# my-cnc.net
KiCad netlist of a schematic drawn in Altium Designer
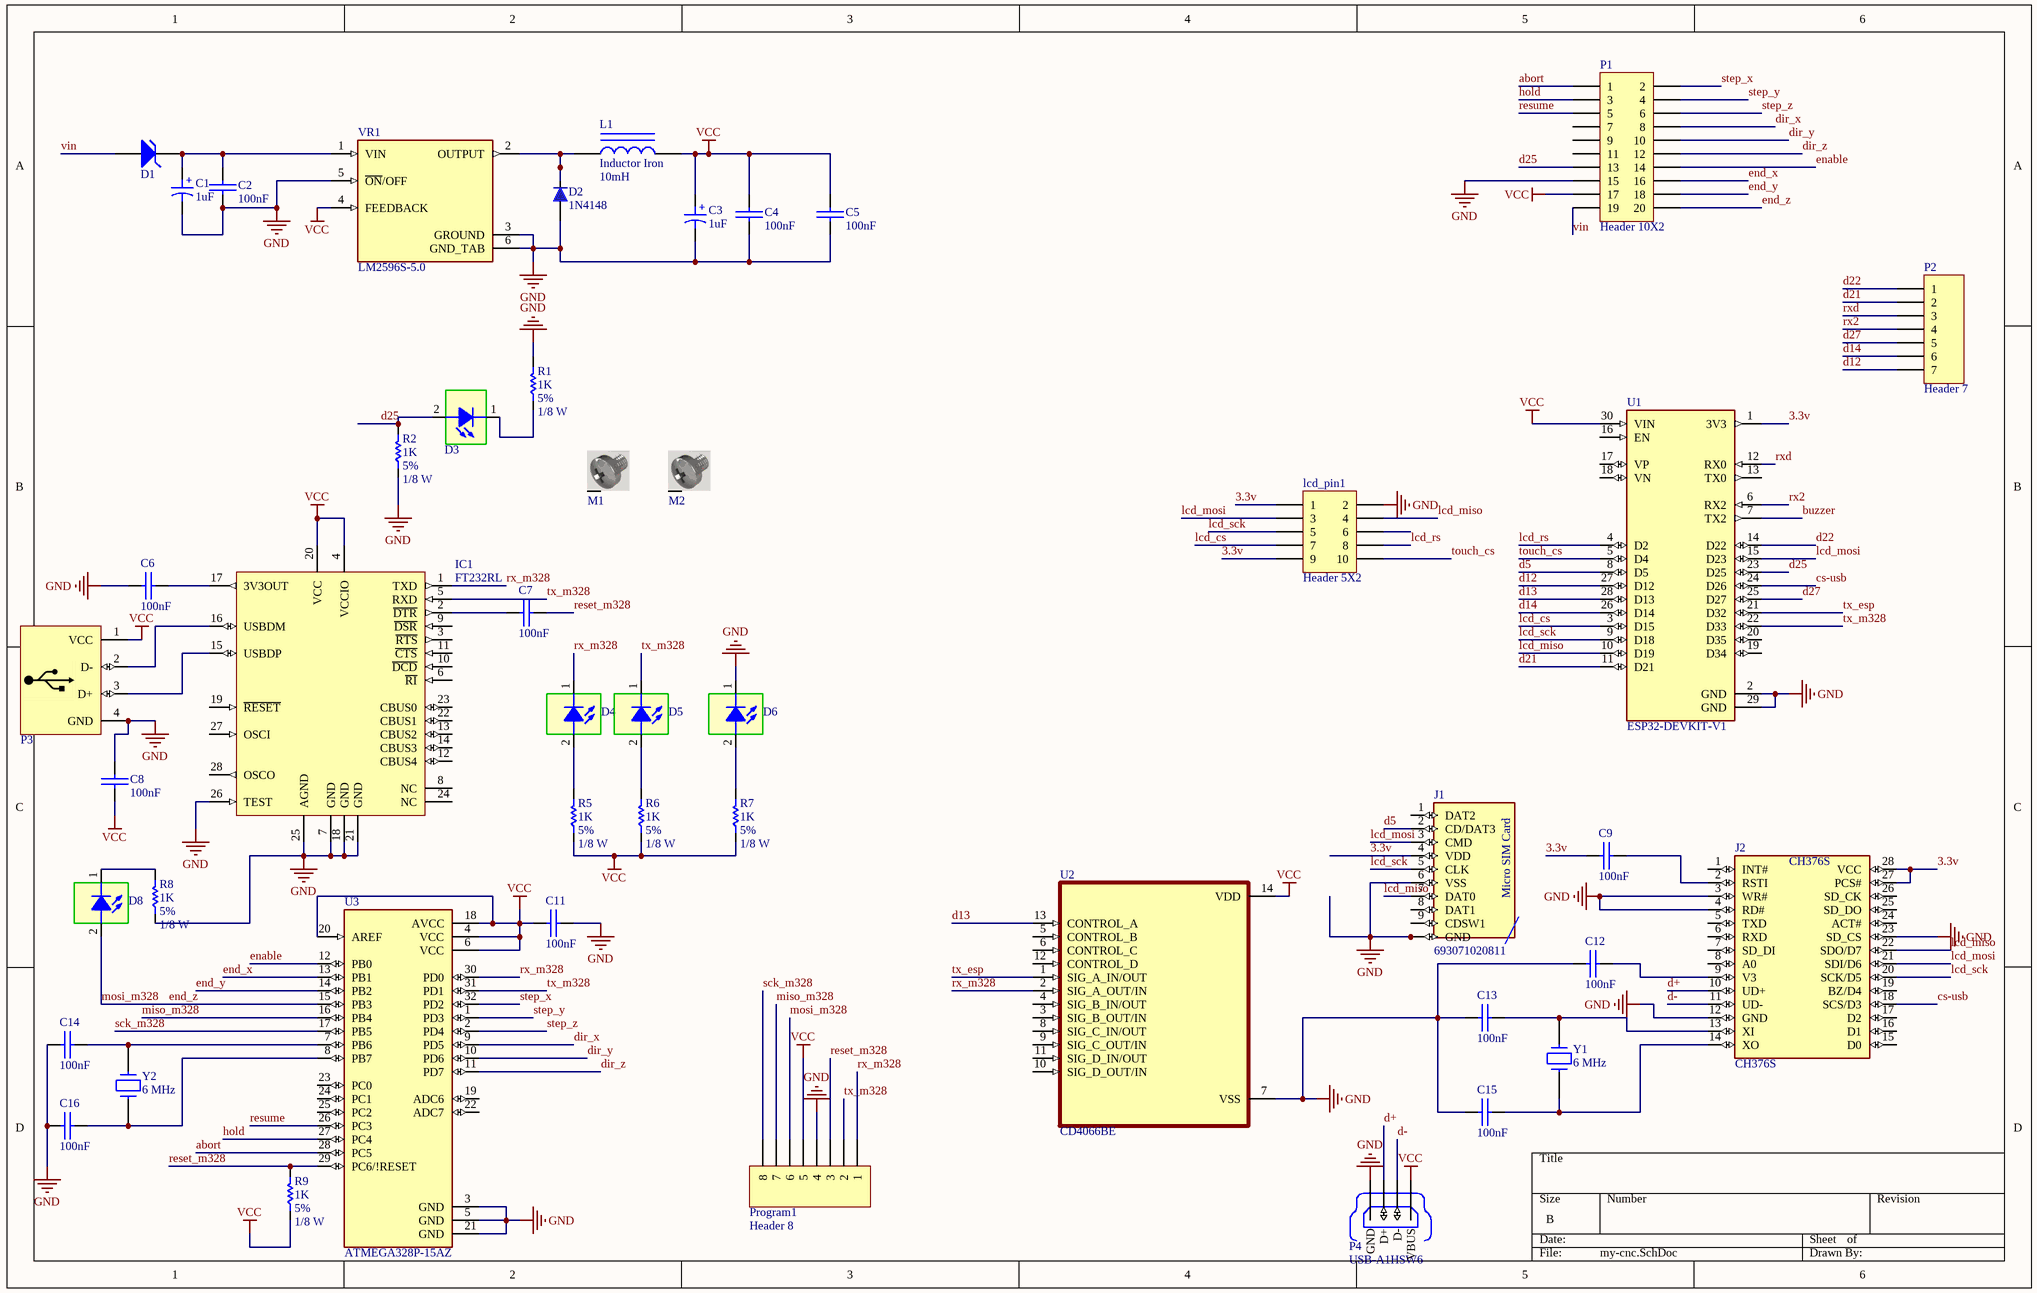
[diagram p0: my-cnc.SchDoc]

(export (version "E")
  (design (tool "Eeschema 10.0.6"))
  (components
    (comp (ref "C1")
      (value "1uF")
      (footprint "CAP SMD 470uF")
      (description "Cap electrolitic radial")
      (fields (field (name "DESIGNER") "Abbas Basereh"))
      (libsource (lib "Altium") (part "Cap ELECTROLITIC TOTAL SIZE"))
    )
    (comp (ref "C2")
      (value "100nF")
      (footprint "SMD_CAP_1206")
      (description "Bipolar Capacitor")
      (fields (field (name "VOLTAGE") "100V") (field (name "DESIGNER") "Saeid Jorablo"))
      (libsource (lib "My_Library") (part "Cap-Bipolar"))
    )
    (comp (ref "C3")
      (value "1uF")
      (footprint "CAP SMD 470uF")
      (description "Cap electrolitic radial")
      (fields (field (name "DESIGNER") "Abbas Basereh"))
      (libsource (lib "Altium") (part "Cap ELECTROLITIC TOTAL SIZE"))
    )
    (comp (ref "C4")
      (value "100nF")
      (footprint "SMD_CAP_1206")
      (description "Bipolar Capacitor")
      (fields (field (name "VOLTAGE") "100V") (field (name "DESIGNER") "Saeid Jorablo"))
      (libsource (lib "My_Library") (part "Cap-Bipolar"))
    )
    (comp (ref "C5")
      (value "100nF")
      (footprint "SMD_CAP_1206")
      (description "Bipolar Capacitor")
      (fields (field (name "VOLTAGE") "100V") (field (name "DESIGNER") "Saeid Jorablo"))
      (libsource (lib "My_Library") (part "Cap-Bipolar"))
    )
    (comp (ref "C6")
      (value "100nF")
      (footprint "SMD_CAP_1206")
      (description "Bipolar Capacitor")
      (fields (field (name "VOLTAGE") "100V") (field (name "DESIGNER") "Saeid Jorablo"))
      (libsource (lib "My_Library") (part "Cap-Bipolar"))
    )
    (comp (ref "C7")
      (value "100nF")
      (footprint "SMD_CAP_1206")
      (description "Bipolar Capacitor")
      (fields (field (name "VOLTAGE") "100V") (field (name "DESIGNER") "Saeid Jorablo"))
      (libsource (lib "My_Library") (part "Cap-Bipolar"))
    )
    (comp (ref "C8")
      (value "100nF")
      (footprint "SMD_CAP_1206")
      (description "Bipolar Capacitor")
      (fields (field (name "VOLTAGE") "100V") (field (name "DESIGNER") "Saeid Jorablo"))
      (libsource (lib "My_Library") (part "Cap-Bipolar"))
    )
    (comp (ref "C9")
      (value "100nF")
      (footprint "SMD_CAP_1206")
      (description "Bipolar Capacitor")
      (fields (field (name "VOLTAGE") "100V") (field (name "DESIGNER") "Saeid Jorablo"))
      (libsource (lib "My_Library") (part "Cap-Bipolar"))
    )
    (comp (ref "C11")
      (value "100nF")
      (footprint "SMD_CAP_1206")
      (description "Bipolar Capacitor")
      (fields (field (name "VOLTAGE") "100V") (field (name "DESIGNER") "Saeid Jorablo"))
      (libsource (lib "My_Library") (part "Cap-Bipolar"))
    )
    (comp (ref "C12")
      (value "100nF")
      (footprint "SMD_CAP_1206")
      (description "Bipolar Capacitor")
      (fields (field (name "VOLTAGE") "100V") (field (name "DESIGNER") "Saeid Jorablo"))
      (libsource (lib "My_Library") (part "Cap-Bipolar"))
    )
    (comp (ref "C13")
      (value "100nF")
      (footprint "SMD_CAP_1206")
      (description "Bipolar Capacitor")
      (fields (field (name "VOLTAGE") "100V") (field (name "DESIGNER") "Saeid Jorablo"))
      (libsource (lib "My_Library") (part "Cap-Bipolar"))
    )
    (comp (ref "C14")
      (value "100nF")
      (footprint "SMD_CAP_1206")
      (description "Bipolar Capacitor")
      (fields (field (name "VOLTAGE") "100V") (field (name "DESIGNER") "Saeid Jorablo"))
      (libsource (lib "My_Library") (part "Cap-Bipolar"))
    )
    (comp (ref "C15")
      (value "100nF")
      (footprint "SMD_CAP_1206")
      (description "Bipolar Capacitor")
      (fields (field (name "VOLTAGE") "100V") (field (name "DESIGNER") "Saeid Jorablo"))
      (libsource (lib "My_Library") (part "Cap-Bipolar"))
    )
    (comp (ref "C16")
      (value "100nF")
      (footprint "SMD_CAP_1206")
      (description "Bipolar Capacitor")
      (fields (field (name "VOLTAGE") "100V") (field (name "DESIGNER") "Saeid Jorablo"))
      (libsource (lib "My_Library") (part "Cap-Bipolar"))
    )
    (comp (ref "D1")
      (value "Diode Zener")
      (footprint "Diode 1W")
      (description "Zener Diode")
      (fields (field (name "VOLTAGE") "3.3 V") (field (name "DESIGNER") "Saeid Jorablo"))
      (libsource (lib "My_Library") (part "Diode Zener"))
    )
    (comp (ref "D2")
      (value "1N4148")
      (footprint "Diode 1n4148 SMD")
      (description "General Semicoductor")
      (libsource (lib "Altium") (part "1N4148 SMD"))
    )
    (comp (ref "D3")
      (value "SMD 1206 LED")
      (footprint "LED 1206")
      (libsource (lib "") (part "LED SMD 1206_1"))
    )
    (comp (ref "D4")
      (value "SMD 1206 LED")
      (footprint "LED 1206")
      (libsource (lib "Altium") (part "LED SMD 1206"))
    )
    (comp (ref "D5")
      (value "SMD 1206 LED")
      (footprint "LED 1206")
      (libsource (lib "Altium") (part "LED SMD 1206"))
    )
    (comp (ref "D6")
      (value "SMD 1206 LED")
      (footprint "LED 1206")
      (libsource (lib "Altium") (part "LED SMD 1206"))
    )
    (comp (ref "D8")
      (value "SMD 1206 LED")
      (footprint "LED 1206")
      (libsource (lib "Altium") (part "LED SMD 1206"))
    )
    (comp (ref "IC1")
      (value "FT232RL")
      (footprint "SSOP-28_L")
      (description "USB UART Asynchronous Serial Data Transfer Chip, SSOP-28, Tape and Reel")
      (fields (field (name "PUBLISHER") "Altium Limited"))
      (libsource (lib "Altium") (part "FT232RL"))
    )
    (comp (ref "J1")
      (value "693071020811")
      (footprint "693071020811")
      (description "9 (8 + 1) Position Card Connector Secure Digital - microSDâ„¢ Surface Mount, Right Angle Gold")
      (fields (field (name "MF") "Wurth Electronics"))
      (libsource (lib "693071020811") (part "693071020811"))
    )
    (comp (ref "J2")
      (value "CH376S")
      (footprint "SOP28")
      (description "File manage control chip. Small outline package of 28-pin")
      (fields (field (name "MF") "WCH"))
      (libsource (lib "CH376S") (part "CH376S"))
    )
    (comp (ref "L1")
      (value "Inductor Iron")
      (footprint "AXIAL-0.9")
      (description "Magnetic-Core Inductor")
      (fields (field (name "ALTIUM_VALUE") "10mH") (field (name "PUBLISHER") "Altium Limited"))
      (libsource (lib "Miscellaneous Devices") (part "Inductor Iron"))
    )
    (comp (ref "lcd_pin1")
      (value "Header 5X2")
      (footprint "HDR2X5")
      (description "Header, 5-Pin, Dual row")
      (fields (field (name "PUBLISHER") "Altium Limited"))
      (libsource (lib "Miscellaneous Connectors") (part "Header 5X2"))
    )
    (comp (ref "M1")
      (value "Screw")
      (footprint "Board Screw")
      (description "Board Screw With Spacer")
      (libsource (lib "My_Library") (part "Board Screw"))
    )
    (comp (ref "M2")
      (value "Screw")
      (footprint "Board Screw")
      (description "Board Screw With Spacer")
      (libsource (lib "My_Library") (part "Board Screw"))
    )
    (comp (ref "P1")
      (value "Header 10X2")
      (footprint "HDR2X10")
      (description "Header, 10-Pin, Dual row")
      (fields (field (name "PUBLISHER") "Altium Limited"))
      (libsource (lib "Miscellaneous Connectors") (part "Header 10X2"))
    )
    (comp (ref "P2")
      (value "Header 7")
      (footprint "HDR1X7")
      (description "Header, 7-Pin")
      (fields (field (name "PUBLISHER") "Altium Limited"))
      (libsource (lib "Miscellaneous Connectors") (part "Header 7"))
    )
    (comp (ref "P3")
      (value "USB Connector")
      (footprint "USB2.5-2H4F")
      (description "USB Connector-B Type")
      (libsource (lib "Altium") (part "USB B-Type"))
    )
    (comp (ref "P4")
      (value "USB-A1HSW6")
      (footprint "OST_USB-A1HSW6")
      (description "USB-A (USB TYPE-A) - Receptacle Connector 4 Position Through Hole, Right Angle")
      (fields (field (name "MF") "On Shore"))
      (libsource (lib "USB-A1HSW6") (part "USB-A1HSW6"))
    )
    (comp (ref "Program1")
      (value "Header 8")
      (footprint "HDR1X8")
      (description "Header, 8-Pin")
      (fields (field (name "PUBLISHER") "Altium Limited"))
      (libsource (lib "Miscellaneous Connectors") (part "Header 8"))
    )
    (comp (ref "R1")
      (value "1K")
      (footprint "RES 1206 (3216X08L)")
      (description "Resistor")
      (fields (field (name "TOLERANCE") "5%") (field (name "POWER") "1/8 W"))
      (libsource (lib "My_Library") (part "Resistor"))
    )
    (comp (ref "R2")
      (value "1K")
      (footprint "RES 1206 (3216X08L)")
      (description "Resistor")
      (fields (field (name "TOLERANCE") "5%") (field (name "POWER") "1/8 W"))
      (libsource (lib "My_Library") (part "Resistor"))
    )
    (comp (ref "R5")
      (value "1K")
      (footprint "RES 1206 (3216X08L)")
      (description "Resistor")
      (fields (field (name "TOLERANCE") "5%") (field (name "POWER") "1/8 W"))
      (libsource (lib "My_Library") (part "Resistor"))
    )
    (comp (ref "R6")
      (value "1K")
      (footprint "RES 1206 (3216X08L)")
      (description "Resistor")
      (fields (field (name "TOLERANCE") "5%") (field (name "POWER") "1/8 W"))
      (libsource (lib "My_Library") (part "Resistor"))
    )
    (comp (ref "R7")
      (value "1K")
      (footprint "RES 1206 (3216X08L)")
      (description "Resistor")
      (fields (field (name "TOLERANCE") "5%") (field (name "POWER") "1/8 W"))
      (libsource (lib "My_Library") (part "Resistor"))
    )
    (comp (ref "R8")
      (value "1K")
      (footprint "RES 1206 (3216X08L)")
      (description "Resistor")
      (fields (field (name "TOLERANCE") "5%") (field (name "POWER") "1/8 W"))
      (libsource (lib "My_Library") (part "Resistor"))
    )
    (comp (ref "R9")
      (value "1K")
      (footprint "RES 1206 (3216X08L)")
      (description "Resistor")
      (fields (field (name "TOLERANCE") "5%") (field (name "POWER") "1/8 W"))
      (libsource (lib "My_Library") (part "Resistor"))
    )
    (comp (ref "U1")
      (value "ESP32-DEVKIT-V1")
      (footprint "MODULE_ESP32_DEVKIT_V1")
      (fields (field (name "MF") "Do it"))
      (libsource (lib "ESP32-DEVKIT-V1") (part "ESP32-DEVKIT-V1"))
    )
    (comp (ref "U2")
      (value "CD4066BE")
      (footprint "DIP794W45P254L1969H508Q14")
      (description "10-pA on-state leakage current, 20-V, 1:1 (SPST), 4-channel analog switch")
      (fields (field (name "MF") "Texas Instruments"))
      (libsource (lib "CD4066BE") (part "CD4066BE"))
    )
    (comp (ref "U3")
      (value "ATMEGA328P-15AZ")
      (footprint "QFP80P900X900X120-32N")
      (fields (field (name "MF") "Microchip") (field (name "DIGI-KEY_PART_NUMBER") "ATMEGA328P-15AZCT-ND"))
      (libsource (lib "ATMEGA328P-15AZ") (part "ATMEGA328P-15AZ"))
    )
    (comp (ref "VR1")
      (value "LM2596S-5.0")
      (footprint "LM2596S-5.0:TO170P1524X483-6N")
      (libsource (lib "LM2596S-5.0") (part "LM2596S-5.0"))
    )
    (comp (ref "Y1")
      (value "6 MHz")
      (footprint "My_Crystal")
      (description "Crystal")
      (libsource (lib "Devices") (part "CRYSTAL"))
    )
    (comp (ref "Y2")
      (value "6 MHz")
      (footprint "My_Crystal")
      (description "Crystal")
      (libsource (lib "Devices") (part "CRYSTAL"))
    )
  )
  (nets
    (net (code "1") (name "/3.3v") (class "Default")
      (node (ref "C9") (pin "2") (pinfunction "-_2") (pintype "passive"))
      (node (ref "J1") (pin "4") (pinfunction "VDD_4") (pintype "bidirectional"))
      (node (ref "J2") (pin "27") (pinfunction "PCS#_27") (pintype "bidirectional"))
      (node (ref "J2") (pin "28") (pinfunction "VCC_28") (pintype "bidirectional"))
      (node (ref "U1") (pin "1") (pinfunction "3V3_1") (pintype "output"))
      (node (ref "lcd_pin1") (pin "1") (pinfunction "1_1") (pintype "passive"))
      (node (ref "lcd_pin1") (pin "9") (pinfunction "9_9") (pintype "passive"))
    )
    (net (code "2") (name "/abort") (class "Default")
      (node (ref "P1") (pin "1") (pinfunction "1_1") (pintype "passive"))
      (node (ref "U3") (pin "28") (pinfunction "PC5_28") (pintype "bidirectional"))
    )
    (net (code "3") (name "/buzzer") (class "Default")
      (node (ref "U1") (pin "7") (pinfunction "TX2_7") (pintype "output"))
    )
    (net (code "4") (name "/cs-usb") (class "Default")
      (node (ref "J2") (pin "18") (pinfunction "SCS/D3_18") (pintype "bidirectional"))
      (node (ref "U1") (pin "24") (pinfunction "D26_24") (pintype "bidirectional"))
    )
    (net (code "5") (name "/d+") (class "Default")
      (node (ref "J2") (pin "10") (pinfunction "UD+_10") (pintype "bidirectional"))
      (node (ref "P4") (pin "3") (pinfunction "D+_3") (pintype "bidirectional"))
    )
    (net (code "6") (name "/d-") (class "Default")
      (node (ref "J2") (pin "11") (pinfunction "UD-_11") (pintype "bidirectional"))
      (node (ref "P4") (pin "2") (pinfunction "D-_2") (pintype "bidirectional"))
    )
    (net (code "7") (name "/d5") (class "Default")
      (node (ref "J1") (pin "2") (pinfunction "CD/DAT3_2") (pintype "bidirectional"))
      (node (ref "U1") (pin "8") (pinfunction "D5_8") (pintype "bidirectional"))
    )
    (net (code "8") (name "/d12") (class "Default")
      (node (ref "P2") (pin "7") (pinfunction "7_7") (pintype "passive"))
      (node (ref "U1") (pin "27") (pinfunction "D12_27") (pintype "bidirectional"))
    )
    (net (code "9") (name "/d13") (class "Default")
      (node (ref "U1") (pin "28") (pinfunction "D13_28") (pintype "bidirectional"))
      (node (ref "U2") (pin "13") (pinfunction "CONTROL_A_13") (pintype "input"))
    )
    (net (code "10") (name "/d14") (class "Default")
      (node (ref "P2") (pin "6") (pinfunction "6_6") (pintype "passive"))
      (node (ref "U1") (pin "26") (pinfunction "D14_26") (pintype "bidirectional"))
    )
    (net (code "11") (name "/d21") (class "Default")
      (node (ref "P2") (pin "2") (pinfunction "2_2") (pintype "passive"))
      (node (ref "U1") (pin "11") (pinfunction "D21_11") (pintype "bidirectional"))
    )
    (net (code "12") (name "/d22") (class "Default")
      (node (ref "P2") (pin "1") (pinfunction "1_1") (pintype "passive"))
      (node (ref "U1") (pin "14") (pinfunction "D22_14") (pintype "bidirectional"))
    )
    (net (code "13") (name "/d25") (class "Default")
      (node (ref "D3") (pin "2") (pinfunction "2_2") (pintype "passive"))
      (node (ref "P1") (pin "13") (pinfunction "13_13") (pintype "passive"))
      (node (ref "R2") (pin "2") (pinfunction "2_2") (pintype "passive"))
      (node (ref "U1") (pin "23") (pinfunction "D25_23") (pintype "bidirectional"))
    )
    (net (code "14") (name "/d27") (class "Default")
      (node (ref "P2") (pin "5") (pinfunction "5_5") (pintype "passive"))
      (node (ref "U1") (pin "25") (pinfunction "D27_25") (pintype "bidirectional"))
    )
    (net (code "15") (name "/dir_x") (class "Default")
      (node (ref "P1") (pin "8") (pinfunction "8_8") (pintype "passive"))
      (node (ref "U3") (pin "9") (pinfunction "PD5_9") (pintype "bidirectional"))
    )
    (net (code "16") (name "/dir_y") (class "Default")
      (node (ref "P1") (pin "10") (pinfunction "10_10") (pintype "passive"))
      (node (ref "U3") (pin "10") (pinfunction "PD6_10") (pintype "bidirectional"))
    )
    (net (code "17") (name "/dir_z") (class "Default")
      (node (ref "P1") (pin "12") (pinfunction "12_12") (pintype "passive"))
      (node (ref "U3") (pin "11") (pinfunction "PD7_11") (pintype "bidirectional"))
    )
    (net (code "18") (name "/enable") (class "Default")
      (node (ref "P1") (pin "14") (pinfunction "14_14") (pintype "passive"))
      (node (ref "U3") (pin "12") (pinfunction "PB0_12") (pintype "bidirectional"))
    )
    (net (code "19") (name "/end_x") (class "Default")
      (node (ref "P1") (pin "16") (pinfunction "16_16") (pintype "passive"))
      (node (ref "U3") (pin "13") (pinfunction "PB1_13") (pintype "bidirectional"))
    )
    (net (code "20") (name "/end_y") (class "Default")
      (node (ref "P1") (pin "18") (pinfunction "18_18") (pintype "passive"))
      (node (ref "U3") (pin "14") (pinfunction "PB2_14") (pintype "bidirectional"))
    )
    (net (code "21") (name "/end_z") (class "Default")
      (node (ref "D8") (pin "2") (pinfunction "2_2") (pintype "passive"))
      (node (ref "P1") (pin "20") (pinfunction "20_20") (pintype "passive"))
      (node (ref "Program1") (pin "6") (pinfunction "6_6") (pintype "passive"))
      (node (ref "U3") (pin "15") (pinfunction "PB3_15") (pintype "bidirectional"))
    )
    (net (code "22") (name "/hold") (class "Default")
      (node (ref "P1") (pin "3") (pinfunction "3_3") (pintype "passive"))
      (node (ref "U3") (pin "27") (pinfunction "PC4_27") (pintype "bidirectional"))
    )
    (net (code "23") (name "/lcd_cs") (class "Default")
      (node (ref "U1") (pin "3") (pinfunction "D15_3") (pintype "bidirectional"))
      (node (ref "lcd_pin1") (pin "7") (pinfunction "7_7") (pintype "passive"))
    )
    (net (code "24") (name "/lcd_miso") (class "Default")
      (node (ref "J1") (pin "7") (pinfunction "DAT0_7") (pintype "bidirectional"))
      (node (ref "J2") (pin "22") (pinfunction "SDO/D7_22") (pintype "bidirectional"))
      (node (ref "U1") (pin "10") (pinfunction "D19_10") (pintype "bidirectional"))
      (node (ref "lcd_pin1") (pin "4") (pinfunction "4_4") (pintype "passive"))
    )
    (net (code "25") (name "/lcd_mosi") (class "Default")
      (node (ref "J1") (pin "3") (pinfunction "CMD_3") (pintype "bidirectional"))
      (node (ref "J2") (pin "21") (pinfunction "SDI/D6_21") (pintype "bidirectional"))
      (node (ref "U1") (pin "15") (pinfunction "D23_15") (pintype "bidirectional"))
      (node (ref "lcd_pin1") (pin "3") (pinfunction "3_3") (pintype "passive"))
    )
    (net (code "26") (name "/lcd_rs") (class "Default")
      (node (ref "U1") (pin "4") (pinfunction "D2_4") (pintype "bidirectional"))
      (node (ref "lcd_pin1") (pin "8") (pinfunction "8_8") (pintype "passive"))
    )
    (net (code "27") (name "/lcd_sck") (class "Default")
      (node (ref "J1") (pin "5") (pinfunction "CLK_5") (pintype "bidirectional"))
      (node (ref "J2") (pin "20") (pinfunction "SCK/D5_20") (pintype "bidirectional"))
      (node (ref "U1") (pin "9") (pinfunction "D18_9") (pintype "bidirectional"))
      (node (ref "lcd_pin1") (pin "5") (pinfunction "5_5") (pintype "passive"))
    )
    (net (code "28") (name "/miso_m328") (class "Default")
      (node (ref "Program1") (pin "7") (pinfunction "7_7") (pintype "passive"))
      (node (ref "U3") (pin "16") (pinfunction "PB4_16") (pintype "bidirectional"))
    )
    (net (code "29") (name "/reset_m328") (class "Default")
      (node (ref "C7") (pin "1") (pinfunction "+_1") (pintype "passive"))
      (node (ref "Program1") (pin "3") (pinfunction "3_3") (pintype "passive"))
      (node (ref "R9") (pin "2") (pinfunction "2_2") (pintype "passive"))
      (node (ref "U3") (pin "29") (pinfunction "PC6/!RESET_29") (pintype "bidirectional"))
    )
    (net (code "30") (name "/resume") (class "Default")
      (node (ref "P1") (pin "5") (pinfunction "5_5") (pintype "passive"))
      (node (ref "U3") (pin "26") (pinfunction "PC3_26") (pintype "bidirectional"))
    )
    (net (code "31") (name "/rx2") (class "Default")
      (node (ref "P2") (pin "4") (pinfunction "4_4") (pintype "passive"))
      (node (ref "U1") (pin "6") (pinfunction "RX2_6") (pintype "input"))
    )
    (net (code "32") (name "/rx_m328") (class "Default")
      (node (ref "D4") (pin "1") (pinfunction "1_1") (pintype "passive"))
      (node (ref "IC1") (pin "1") (pinfunction "TXD_1") (pintype "output"))
      (node (ref "Program1") (pin "1") (pinfunction "1_1") (pintype "passive"))
      (node (ref "U2") (pin "2") (pinfunction "SIG_A_OUT/IN_2") (pintype "input"))
      (node (ref "U3") (pin "30") (pinfunction "PD0_30") (pintype "bidirectional"))
    )
    (net (code "33") (name "/rxd") (class "Default")
      (node (ref "P2") (pin "3") (pinfunction "3_3") (pintype "passive"))
      (node (ref "U1") (pin "12") (pinfunction "RX0_12") (pintype "input"))
    )
    (net (code "34") (name "/sck_m328") (class "Default")
      (node (ref "Program1") (pin "8") (pinfunction "8_8") (pintype "passive"))
      (node (ref "U3") (pin "17") (pinfunction "PB5_17") (pintype "bidirectional"))
    )
    (net (code "35") (name "/step_x") (class "Default")
      (node (ref "P1") (pin "2") (pinfunction "2_2") (pintype "passive"))
      (node (ref "U3") (pin "32") (pinfunction "PD2_32") (pintype "bidirectional"))
    )
    (net (code "36") (name "/step_y") (class "Default")
      (node (ref "P1") (pin "4") (pinfunction "4_4") (pintype "passive"))
      (node (ref "U3") (pin "1") (pinfunction "PD3_1") (pintype "bidirectional"))
    )
    (net (code "37") (name "/step_z") (class "Default")
      (node (ref "P1") (pin "6") (pinfunction "6_6") (pintype "passive"))
      (node (ref "U3") (pin "2") (pinfunction "PD4_2") (pintype "bidirectional"))
    )
    (net (code "38") (name "/touch_cs") (class "Default")
      (node (ref "U1") (pin "5") (pinfunction "D4_5") (pintype "bidirectional"))
      (node (ref "lcd_pin1") (pin "10") (pinfunction "10_10") (pintype "passive"))
    )
    (net (code "39") (name "/tx_esp") (class "Default")
      (node (ref "U1") (pin "21") (pinfunction "D32_21") (pintype "bidirectional"))
      (node (ref "U2") (pin "1") (pinfunction "SIG_A_IN/OUT_1") (pintype "input"))
    )
    (net (code "40") (name "/tx_m328") (class "Default")
      (node (ref "D5") (pin "1") (pinfunction "1_1") (pintype "passive"))
      (node (ref "IC1") (pin "5") (pinfunction "RXD_5") (pintype "input"))
      (node (ref "Program1") (pin "2") (pinfunction "2_2") (pintype "passive"))
      (node (ref "U1") (pin "22") (pinfunction "D33_22") (pintype "bidirectional"))
      (node (ref "U3") (pin "31") (pinfunction "PD1_31") (pintype "bidirectional"))
    )
    (net (code "41") (name "/vin") (class "Default")
      (node (ref "D1") (pin "1") (pinfunction "A_1") (pintype "passive"))
      (node (ref "P1") (pin "19") (pinfunction "19_19") (pintype "passive"))
    )
    (net (code "42") (name "GND") (class "Default")
      (node (ref "C1") (pin "2") (pinfunction "2_2") (pintype "passive"))
      (node (ref "C11") (pin "2") (pinfunction "-_2") (pintype "passive"))
      (node (ref "C12") (pin "2") (pinfunction "-_2") (pintype "passive"))
      (node (ref "C13") (pin "2") (pinfunction "-_2") (pintype "passive"))
      (node (ref "C14") (pin "1") (pinfunction "+_1") (pintype "passive"))
      (node (ref "C15") (pin "2") (pinfunction "-_2") (pintype "passive"))
      (node (ref "C16") (pin "1") (pinfunction "+_1") (pintype "passive"))
      (node (ref "C2") (pin "1") (pinfunction "+_1") (pintype "passive"))
      (node (ref "C3") (pin "2") (pinfunction "2_2") (pintype "passive"))
      (node (ref "C4") (pin "1") (pinfunction "+_1") (pintype "passive"))
      (node (ref "C5") (pin "1") (pinfunction "+_1") (pintype "passive"))
      (node (ref "C6") (pin "2") (pinfunction "-_2") (pintype "passive"))
      (node (ref "C8") (pin "1") (pinfunction "+_1") (pintype "passive"))
      (node (ref "D2") (pin "1") (pintype "passive"))
      (node (ref "D6") (pin "1") (pinfunction "1_1") (pintype "passive"))
      (node (ref "IC1") (pin "18") (pinfunction "GND_18") (pintype "power_in"))
      (node (ref "IC1") (pin "21") (pinfunction "GND_21") (pintype "power_in"))
      (node (ref "IC1") (pin "25") (pinfunction "AGND_25") (pintype "power_in"))
      (node (ref "IC1") (pin "26") (pinfunction "TEST_26") (pintype "input"))
      (node (ref "IC1") (pin "7") (pinfunction "GND_7") (pintype "power_in"))
      (node (ref "J1") (pin "10") (pinfunction "GND_10") (pintype "bidirectional"))
      (node (ref "J1") (pin "11") (pinfunction "GND_11") (pintype "bidirectional"))
      (node (ref "J1") (pin "12") (pinfunction "GND_12") (pintype "bidirectional"))
      (node (ref "J1") (pin "13") (pinfunction "GND_13") (pintype "bidirectional"))
      (node (ref "J1") (pin "6") (pinfunction "VSS_6") (pintype "bidirectional"))
      (node (ref "J2") (pin "12") (pinfunction "GND_12") (pintype "bidirectional"))
      (node (ref "J2") (pin "23") (pinfunction "SD_CS_23") (pintype "bidirectional"))
      (node (ref "J2") (pin "3") (pinfunction "WR#_3") (pintype "bidirectional"))
      (node (ref "J2") (pin "4") (pinfunction "RD#_4") (pintype "bidirectional"))
      (node (ref "P1") (pin "15") (pinfunction "15_15") (pintype "passive"))
      (node (ref "P3") (pin "4") (pinfunction "GND_4") (pintype "power_in"))
      (node (ref "P4") (pin "4") (pinfunction "GND_4") (pintype "power_in"))
      (node (ref "Program1") (pin "4") (pinfunction "4_4") (pintype "passive"))
      (node (ref "R1") (pin "2") (pinfunction "2_2") (pintype "passive"))
      (node (ref "R2") (pin "1") (pinfunction "1_1") (pintype "passive"))
      (node (ref "R8") (pin "1") (pinfunction "1_1") (pintype "passive"))
      (node (ref "U1") (pin "2") (pinfunction "GND_2") (pintype "power_in"))
      (node (ref "U1") (pin "29") (pinfunction "GND_29") (pintype "power_in"))
      (node (ref "U2") (pin "7") (pinfunction "VSS_7") (pintype "power_in"))
      (node (ref "U3") (pin "21") (pinfunction "GND_21") (pintype "power_in"))
      (node (ref "U3") (pin "3") (pinfunction "GND_3") (pintype "power_in"))
      (node (ref "U3") (pin "5") (pinfunction "GND_5") (pintype "power_in"))
      (node (ref "VR1") (pin "3") (pinfunction "GROUND_3") (pintype "power_in"))
      (node (ref "VR1") (pin "5") (pinfunction "~{ON}/OFF_5") (pintype "input"))
      (node (ref "VR1") (pin "6") (pinfunction "GND_TAB_6") (pintype "power_in"))
      (node (ref "lcd_pin1") (pin "2") (pinfunction "2_2") (pintype "passive"))
    )
    (net (code "43") (name "Net-(C2--)") (class "Default")
      (node (ref "C1") (pin "1") (pinfunction "1_1") (pintype "passive"))
      (node (ref "C2") (pin "2") (pinfunction "-_2") (pintype "passive"))
      (node (ref "D1") (pin "2") (pinfunction "K_2") (pintype "passive"))
      (node (ref "VR1") (pin "1") (pinfunction "VIN_1") (pintype "input"))
    )
    (net (code "44") (name "Net-(C6-+)") (class "Default")
      (node (ref "C6") (pin "1") (pinfunction "+_1") (pintype "passive"))
      (node (ref "IC1") (pin "17") (pinfunction "3V3OUT_17") (pintype "output"))
    )
    (net (code "45") (name "Net-(C7--)") (class "Default")
      (node (ref "C7") (pin "2") (pinfunction "-_2") (pintype "passive"))
      (node (ref "IC1") (pin "2") (pinfunction "~{DTR}_2") (pintype "output"))
    )
    (net (code "46") (name "Net-(C9-+)") (class "Default")
      (node (ref "C9") (pin "1") (pinfunction "+_1") (pintype "passive"))
      (node (ref "J2") (pin "2") (pinfunction "RSTI_2") (pintype "bidirectional"))
    )
    (net (code "47") (name "Net-(C12-+)") (class "Default")
      (node (ref "C12") (pin "1") (pinfunction "+_1") (pintype "passive"))
      (node (ref "J2") (pin "9") (pinfunction "V3_9") (pintype "bidirectional"))
    )
    (net (code "48") (name "Net-(C13-+)") (class "Default")
      (node (ref "C13") (pin "1") (pinfunction "+_1") (pintype "passive"))
      (node (ref "J2") (pin "13") (pinfunction "XI_13") (pintype "bidirectional"))
      (node (ref "Y1") (pin "2") (pinfunction "2_2") (pintype "passive"))
    )
    (net (code "49") (name "Net-(C14--)") (class "Default")
      (node (ref "C14") (pin "2") (pinfunction "-_2") (pintype "passive"))
      (node (ref "U3") (pin "7") (pinfunction "PB6_7") (pintype "bidirectional"))
      (node (ref "Y2") (pin "2") (pinfunction "2_2") (pintype "passive"))
    )
    (net (code "50") (name "Net-(C15-+)") (class "Default")
      (node (ref "C15") (pin "1") (pinfunction "+_1") (pintype "passive"))
      (node (ref "J2") (pin "14") (pinfunction "XO_14") (pintype "bidirectional"))
      (node (ref "Y1") (pin "1") (pinfunction "1_1") (pintype "passive"))
    )
    (net (code "51") (name "Net-(C16--)") (class "Default")
      (node (ref "C16") (pin "2") (pinfunction "-_2") (pintype "passive"))
      (node (ref "U3") (pin "8") (pinfunction "PB7_8") (pintype "bidirectional"))
      (node (ref "Y2") (pin "1") (pinfunction "1_1") (pintype "passive"))
    )
    (net (code "52") (name "Net-(D3-Pad1)") (class "Default")
      (node (ref "D3") (pin "1") (pinfunction "1_1") (pintype "passive"))
      (node (ref "R1") (pin "1") (pinfunction "1_1") (pintype "passive"))
    )
    (net (code "53") (name "Net-(D4-Pad2)") (class "Default")
      (node (ref "D4") (pin "2") (pinfunction "2_2") (pintype "passive"))
      (node (ref "R5") (pin "2") (pinfunction "2_2") (pintype "passive"))
    )
    (net (code "54") (name "Net-(D5-Pad2)") (class "Default")
      (node (ref "D5") (pin "2") (pinfunction "2_2") (pintype "passive"))
      (node (ref "R6") (pin "2") (pinfunction "2_2") (pintype "passive"))
    )
    (net (code "55") (name "Net-(D6-Pad2)") (class "Default")
      (node (ref "D6") (pin "2") (pinfunction "2_2") (pintype "passive"))
      (node (ref "R7") (pin "2") (pinfunction "2_2") (pintype "passive"))
    )
    (net (code "56") (name "Net-(D8-Pad1)") (class "Default")
      (node (ref "D8") (pin "1") (pinfunction "1_1") (pintype "passive"))
      (node (ref "R8") (pin "2") (pinfunction "2_2") (pintype "passive"))
    )
    (net (code "57") (name "Net-(IC1-USBDM)") (class "Default")
      (node (ref "IC1") (pin "16") (pinfunction "USBDM_16") (pintype "bidirectional"))
      (node (ref "P3") (pin "2") (pinfunction "D-_2") (pintype "bidirectional"))
    )
    (net (code "58") (name "Net-(IC1-USBDP)") (class "Default")
      (node (ref "IC1") (pin "15") (pinfunction "USBDP_15") (pintype "bidirectional"))
      (node (ref "P3") (pin "3") (pinfunction "D+_3") (pintype "bidirectional"))
    )
    (net (code "59") (name "Net-(VR1-OUTPUT)") (class "Default")
      (node (ref "D2") (pin "2") (pintype "passive"))
      (node (ref "L1") (pin "1") (pinfunction "1_1") (pintype "passive"))
      (node (ref "VR1") (pin "2") (pinfunction "OUTPUT_2") (pintype "output"))
    )
    (net (code "60") (name "VCC") (class "Default")
      (node (ref "C11") (pin "1") (pinfunction "+_1") (pintype "passive"))
      (node (ref "C3") (pin "1") (pinfunction "1_1") (pintype "passive"))
      (node (ref "C4") (pin "2") (pinfunction "-_2") (pintype "passive"))
      (node (ref "C5") (pin "2") (pinfunction "-_2") (pintype "passive"))
      (node (ref "C8") (pin "2") (pinfunction "-_2") (pintype "passive"))
      (node (ref "IC1") (pin "20") (pinfunction "VCC_20") (pintype "power_in"))
      (node (ref "IC1") (pin "4") (pinfunction "VCCIO_4") (pintype "power_in"))
      (node (ref "L1") (pin "2") (pinfunction "2_2") (pintype "passive"))
      (node (ref "P1") (pin "17") (pinfunction "17_17") (pintype "passive"))
      (node (ref "P3") (pin "1") (pinfunction "VCC_1") (pintype "power_in"))
      (node (ref "P4") (pin "1") (pinfunction "VBUS_1") (pintype "power_in"))
      (node (ref "Program1") (pin "5") (pinfunction "5_5") (pintype "passive"))
      (node (ref "R5") (pin "1") (pinfunction "1_1") (pintype "passive"))
      (node (ref "R6") (pin "1") (pinfunction "1_1") (pintype "passive"))
      (node (ref "R7") (pin "1") (pinfunction "1_1") (pintype "passive"))
      (node (ref "R9") (pin "1") (pinfunction "1_1") (pintype "passive"))
      (node (ref "U1") (pin "30") (pinfunction "VIN_30") (pintype "input"))
      (node (ref "U2") (pin "14") (pinfunction "VDD_14") (pintype "power_in"))
      (node (ref "U3") (pin "18") (pinfunction "AVCC_18") (pintype "power_in"))
      (node (ref "U3") (pin "20") (pinfunction "AREF_20") (pintype "input"))
      (node (ref "U3") (pin "4") (pinfunction "VCC_4") (pintype "power_in"))
      (node (ref "U3") (pin "6") (pinfunction "VCC_6") (pintype "power_in"))
      (node (ref "VR1") (pin "4") (pinfunction "FEEDBACK_4") (pintype "input"))
    )
    (net (code "61") (name "unconnected-(IC1-CBUS0-Pad23)") (class "Default")
      (node (ref "IC1") (pin "23") (pinfunction "CBUS0_23") (pintype "bidirectional"))
    )
    (net (code "62") (name "unconnected-(IC1-CBUS1-Pad22)") (class "Default")
      (node (ref "IC1") (pin "22") (pinfunction "CBUS1_22") (pintype "bidirectional"))
    )
    (net (code "63") (name "unconnected-(IC1-CBUS2-Pad13)") (class "Default")
      (node (ref "IC1") (pin "13") (pinfunction "CBUS2_13") (pintype "bidirectional"))
    )
    (net (code "64") (name "unconnected-(IC1-CBUS3-Pad14)") (class "Default")
      (node (ref "IC1") (pin "14") (pinfunction "CBUS3_14") (pintype "bidirectional"))
    )
    (net (code "65") (name "unconnected-(IC1-CBUS4-Pad12)") (class "Default")
      (node (ref "IC1") (pin "12") (pinfunction "CBUS4_12") (pintype "bidirectional"))
    )
    (net (code "66") (name "unconnected-(IC1-NC-Pad8)") (class "Default")
      (node (ref "IC1") (pin "8") (pinfunction "NC_8") (pintype "passive"))
    )
    (net (code "67") (name "unconnected-(IC1-NC-Pad24)") (class "Default")
      (node (ref "IC1") (pin "24") (pinfunction "NC_24") (pintype "passive"))
    )
    (net (code "68") (name "unconnected-(IC1-OSCI-Pad27)") (class "Default")
      (node (ref "IC1") (pin "27") (pinfunction "OSCI_27") (pintype "input"))
    )
    (net (code "69") (name "unconnected-(IC1-OSCO-Pad28)") (class "Default")
      (node (ref "IC1") (pin "28") (pinfunction "OSCO_28") (pintype "output"))
    )
    (net (code "70") (name "unconnected-(IC1-~{CTS}-Pad11)") (class "Default")
      (node (ref "IC1") (pin "11") (pinfunction "~{CTS}_11") (pintype "input"))
    )
    (net (code "71") (name "unconnected-(IC1-~{DCD}-Pad10)") (class "Default")
      (node (ref "IC1") (pin "10") (pinfunction "~{DCD}_10") (pintype "input"))
    )
    (net (code "72") (name "unconnected-(IC1-~{DSR}-Pad9)") (class "Default")
      (node (ref "IC1") (pin "9") (pinfunction "~{DSR}_9") (pintype "input"))
    )
    (net (code "73") (name "unconnected-(IC1-~{RESET}-Pad19)") (class "Default")
      (node (ref "IC1") (pin "19") (pinfunction "~{RESET}_19") (pintype "input"))
    )
    (net (code "74") (name "unconnected-(IC1-~{RI}-Pad6)") (class "Default")
      (node (ref "IC1") (pin "6") (pinfunction "~{RI}_6") (pintype "input"))
    )
    (net (code "75") (name "unconnected-(IC1-~{RTS}-Pad3)") (class "Default")
      (node (ref "IC1") (pin "3") (pinfunction "~{RTS}_3") (pintype "output"))
    )
    (net (code "76") (name "unconnected-(J1-CDSW1-Pad9)") (class "Default")
      (node (ref "J1") (pin "9") (pinfunction "CDSW1_9") (pintype "bidirectional"))
    )
    (net (code "77") (name "unconnected-(J1-DAT1-Pad8)") (class "Default")
      (node (ref "J1") (pin "8") (pinfunction "DAT1_8") (pintype "bidirectional"))
    )
    (net (code "78") (name "unconnected-(J1-DAT2-Pad1)") (class "Default")
      (node (ref "J1") (pin "1") (pinfunction "DAT2_1") (pintype "bidirectional"))
    )
    (net (code "79") (name "unconnected-(J2-A0-Pad8)") (class "Default")
      (node (ref "J2") (pin "8") (pinfunction "A0_8") (pintype "bidirectional"))
    )
    (net (code "80") (name "unconnected-(J2-ACT#-Pad24)") (class "Default")
      (node (ref "J2") (pin "24") (pinfunction "ACT#_24") (pintype "bidirectional"))
    )
    (net (code "81") (name "unconnected-(J2-BZ{slash}D4-Pad19)") (class "Default")
      (node (ref "J2") (pin "19") (pinfunction "BZ/D4_19") (pintype "bidirectional"))
    )
    (net (code "82") (name "unconnected-(J2-D0-Pad15)") (class "Default")
      (node (ref "J2") (pin "15") (pinfunction "D0_15") (pintype "bidirectional"))
    )
    (net (code "83") (name "unconnected-(J2-D1-Pad16)") (class "Default")
      (node (ref "J2") (pin "16") (pinfunction "D1_16") (pintype "bidirectional"))
    )
    (net (code "84") (name "unconnected-(J2-D2-Pad17)") (class "Default")
      (node (ref "J2") (pin "17") (pinfunction "D2_17") (pintype "bidirectional"))
    )
    (net (code "85") (name "unconnected-(J2-INT#-Pad1)") (class "Default")
      (node (ref "J2") (pin "1") (pinfunction "INT#_1") (pintype "bidirectional"))
    )
    (net (code "86") (name "unconnected-(J2-RXD-Pad6)") (class "Default")
      (node (ref "J2") (pin "6") (pinfunction "RXD_6") (pintype "bidirectional"))
    )
    (net (code "87") (name "unconnected-(J2-SD_CK-Pad26)") (class "Default")
      (node (ref "J2") (pin "26") (pinfunction "SD_CK_26") (pintype "bidirectional"))
    )
    (net (code "88") (name "unconnected-(J2-SD_DI-Pad7)") (class "Default")
      (node (ref "J2") (pin "7") (pinfunction "SD_DI_7") (pintype "bidirectional"))
    )
    (net (code "89") (name "unconnected-(J2-SD_DO-Pad25)") (class "Default")
      (node (ref "J2") (pin "25") (pinfunction "SD_DO_25") (pintype "bidirectional"))
    )
    (net (code "90") (name "unconnected-(J2-TXD-Pad5)") (class "Default")
      (node (ref "J2") (pin "5") (pinfunction "TXD_5") (pintype "bidirectional"))
    )
    (net (code "91") (name "unconnected-(M1-PadS)") (class "Default")
      (node (ref "M1") (pin "S") (pinfunction "S_S") (pintype "passive"))
    )
    (net (code "92") (name "unconnected-(M2-PadS)") (class "Default")
      (node (ref "M2") (pin "S") (pinfunction "S_S") (pintype "passive"))
    )
    (net (code "93") (name "unconnected-(P1-Pad7)") (class "Default")
      (node (ref "P1") (pin "7") (pinfunction "7_7") (pintype "passive"))
    )
    (net (code "94") (name "unconnected-(P1-Pad9)") (class "Default")
      (node (ref "P1") (pin "9") (pinfunction "9_9") (pintype "passive"))
    )
    (net (code "95") (name "unconnected-(P1-Pad11)") (class "Default")
      (node (ref "P1") (pin "11") (pinfunction "11_11") (pintype "passive"))
    )
    (net (code "96") (name "unconnected-(U1-D34-Pad19)") (class "Default")
      (node (ref "U1") (pin "19") (pinfunction "D34_19") (pintype "bidirectional"))
    )
    (net (code "97") (name "unconnected-(U1-D35-Pad20)") (class "Default")
      (node (ref "U1") (pin "20") (pinfunction "D35_20") (pintype "bidirectional"))
    )
    (net (code "98") (name "unconnected-(U1-EN-Pad16)") (class "Default")
      (node (ref "U1") (pin "16") (pinfunction "EN_16") (pintype "input"))
    )
    (net (code "99") (name "unconnected-(U1-TX0-Pad13)") (class "Default")
      (node (ref "U1") (pin "13") (pinfunction "TX0_13") (pintype "output"))
    )
    (net (code "100") (name "unconnected-(U1-VN-Pad18)") (class "Default")
      (node (ref "U1") (pin "18") (pinfunction "VN_18") (pintype "bidirectional"))
    )
    (net (code "101") (name "unconnected-(U1-VP-Pad17)") (class "Default")
      (node (ref "U1") (pin "17") (pinfunction "VP_17") (pintype "bidirectional"))
    )
    (net (code "102") (name "unconnected-(U2-CONTROL_B-Pad5)") (class "Default")
      (node (ref "U2") (pin "5") (pinfunction "CONTROL_B_5") (pintype "input"))
    )
    (net (code "103") (name "unconnected-(U2-CONTROL_C-Pad6)") (class "Default")
      (node (ref "U2") (pin "6") (pinfunction "CONTROL_C_6") (pintype "input"))
    )
    (net (code "104") (name "unconnected-(U2-CONTROL_D-Pad12)") (class "Default")
      (node (ref "U2") (pin "12") (pinfunction "CONTROL_D_12") (pintype "input"))
    )
    (net (code "105") (name "unconnected-(U2-SIG_B_IN{slash}OUT-Pad4)") (class "Default")
      (node (ref "U2") (pin "4") (pinfunction "SIG_B_IN/OUT_4") (pintype "input"))
    )
    (net (code "106") (name "unconnected-(U2-SIG_B_OUT{slash}IN-Pad3)") (class "Default")
      (node (ref "U2") (pin "3") (pinfunction "SIG_B_OUT/IN_3") (pintype "input"))
    )
    (net (code "107") (name "unconnected-(U2-SIG_C_IN{slash}OUT-Pad8)") (class "Default")
      (node (ref "U2") (pin "8") (pinfunction "SIG_C_IN/OUT_8") (pintype "input"))
    )
    (net (code "108") (name "unconnected-(U2-SIG_C_OUT{slash}IN-Pad9)") (class "Default")
      (node (ref "U2") (pin "9") (pinfunction "SIG_C_OUT/IN_9") (pintype "input"))
    )
    (net (code "109") (name "unconnected-(U2-SIG_D_IN{slash}OUT-Pad11)") (class "Default")
      (node (ref "U2") (pin "11") (pinfunction "SIG_D_IN/OUT_11") (pintype "input"))
    )
    (net (code "110") (name "unconnected-(U2-SIG_D_OUT{slash}IN-Pad10)") (class "Default")
      (node (ref "U2") (pin "10") (pinfunction "SIG_D_OUT/IN_10") (pintype "input"))
    )
    (net (code "111") (name "unconnected-(U3-ADC6-Pad19)") (class "Default")
      (node (ref "U3") (pin "19") (pinfunction "ADC6_19") (pintype "bidirectional"))
    )
    (net (code "112") (name "unconnected-(U3-ADC7-Pad22)") (class "Default")
      (node (ref "U3") (pin "22") (pinfunction "ADC7_22") (pintype "bidirectional"))
    )
    (net (code "113") (name "unconnected-(U3-PC0-Pad23)") (class "Default")
      (node (ref "U3") (pin "23") (pinfunction "PC0_23") (pintype "bidirectional"))
    )
    (net (code "114") (name "unconnected-(U3-PC1-Pad24)") (class "Default")
      (node (ref "U3") (pin "24") (pinfunction "PC1_24") (pintype "bidirectional"))
    )
    (net (code "115") (name "unconnected-(U3-PC2-Pad25)") (class "Default")
      (node (ref "U3") (pin "25") (pinfunction "PC2_25") (pintype "bidirectional"))
    )
    (net (code "116") (name "unconnected-(lcd_pin1-Pad6)") (class "Default")
      (node (ref "lcd_pin1") (pin "6") (pinfunction "6_6") (pintype "passive"))
    )
  )
)
